# Motor_Interface.net
KiCad netlist of a schematic drawn in Altium Designer
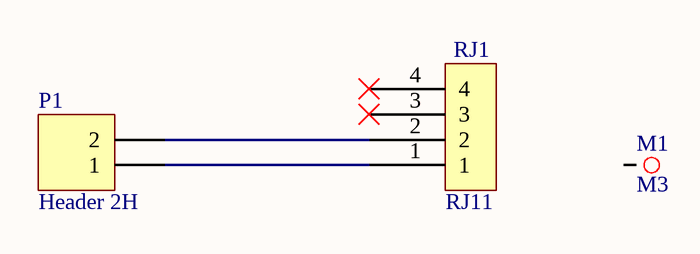
[diagram p0: Motor Interface.SchDoc]

(export (version "E")
  (design (tool "Eeschema 10.0.6"))
  (components
    (comp (ref "M1") (value "M3") (footprint "M") (libsource (lib "QQW-1.SCHLIB") (part "M3")))
    (comp (ref "P1")
      (value "Header 2H")
      (footprint "IO/1")
      (description "Header, 2-Pin, Right Angle")
      (fields (field (name "PUBLISHER") "Altium Limited"))
      (libsource (lib "Miscellaneous Connectors") (part "Header 2H"))
    )
    (comp (ref "RJ1") (value "RJ11") (footprint "IO/2") (libsource (lib "少儿智能车") (part "RJ11")))
  )
  (nets
    (net (code "1") (name "Net-(P1-Pad1)") (class "Default")
      (node (ref "P1") (pin "1") (pinfunction "1_1") (pintype "passive"))
      (node (ref "RJ1") (pin "1") (pinfunction "1_1") (pintype "passive"))
    )
    (net (code "2") (name "Net-(P1-Pad2)") (class "Default")
      (node (ref "P1") (pin "2") (pinfunction "2_2") (pintype "passive"))
      (node (ref "RJ1") (pin "2") (pinfunction "2_2") (pintype "passive"))
    )
    (net (code "3") (name "unconnected-(M1-Pad0)") (class "Default")
      (node (ref "M1") (pin "0") (pinfunction "0_0") (pintype "passive"))
    )
    (net (code "4") (name "unconnected-(RJ1-Pad3)") (class "Default")
      (node (ref "RJ1") (pin "3") (pinfunction "3_3") (pintype "passive+no_connect"))
    )
    (net (code "5") (name "unconnected-(RJ1-Pad4)") (class "Default")
      (node (ref "RJ1") (pin "4") (pinfunction "4_4") (pintype "passive+no_connect"))
    )
  )
)
